# KGGR_D.net
KiCad netlist of a schematic drawn in EAGLE
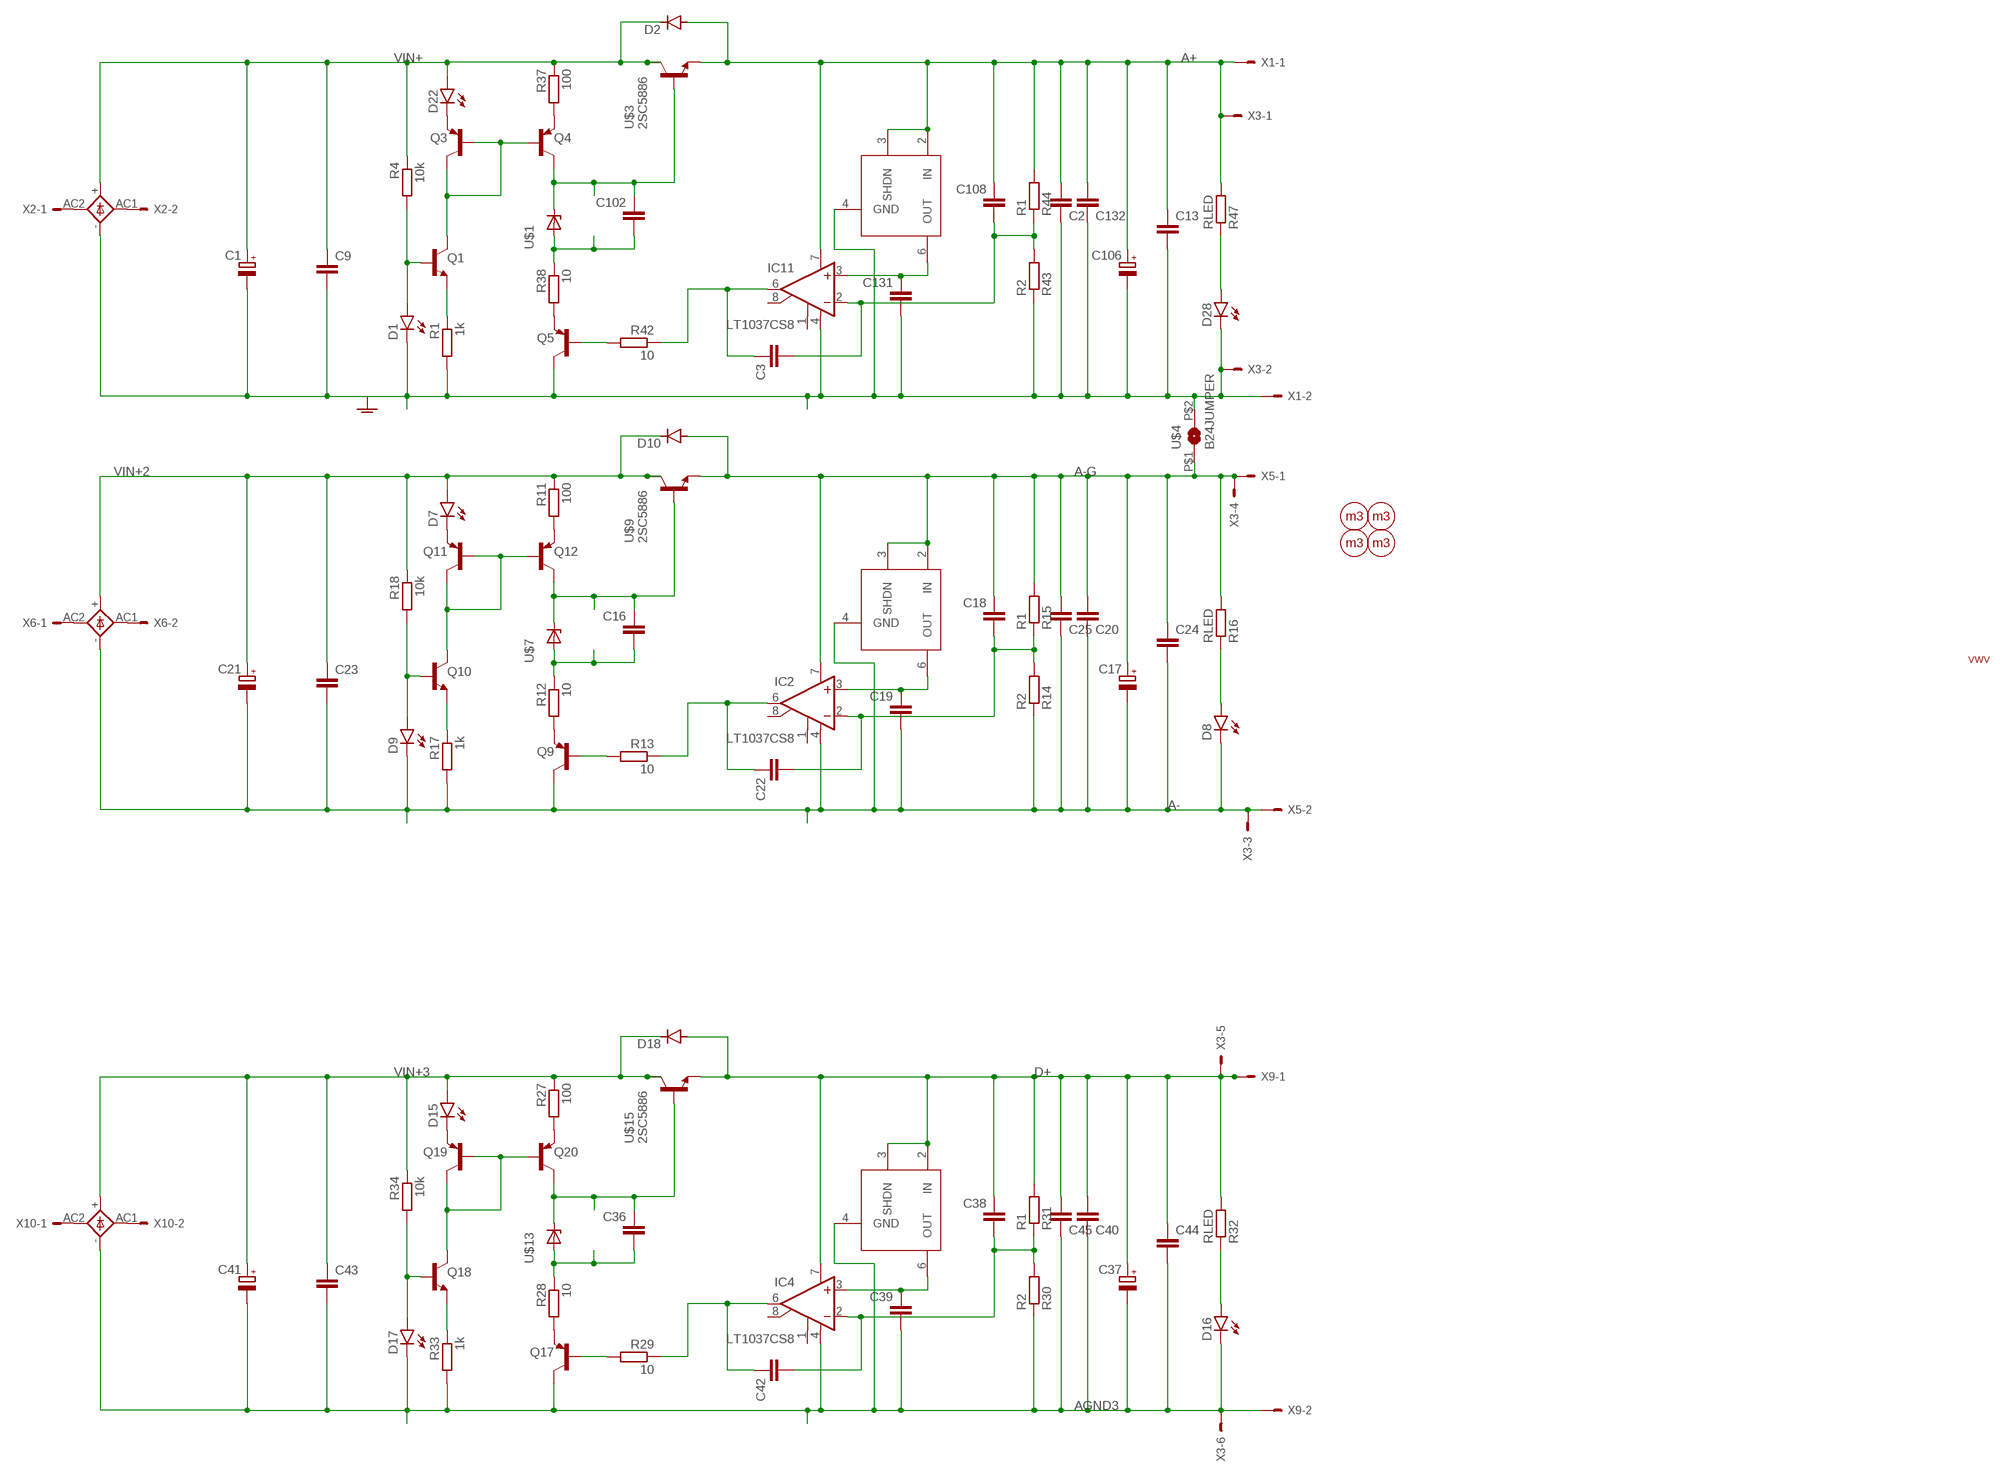
[diagram p0: schematic, sheet 1]

(export (version "E")
  (design (tool "Eeschema 10.0.6"))
  (components
    (comp (ref "B1")
      (value "GBU4")
      (footprint "eagle-import:GBU4S")
      (libsource (lib "eagle-import") (part "GBU4"))
    )
    (comp (ref "B3")
      (value "GBU4")
      (footprint "eagle-import:GBU4S")
      (libsource (lib "eagle-import") (part "GBU4"))
    )
    (comp (ref "B5")
      (value "GBU4")
      (footprint "eagle-import:GBU4S")
      (libsource (lib "eagle-import") (part "GBU4"))
    )
    (comp (ref "C1")
      (value "CPOL-EUE7.5-18")
      (footprint "eagle-import:E7,5-18")
      (libsource (lib "eagle-import") (part "CPOL-EUE7.5-18"))
    )
    (comp (ref "C2")
      (value "C-EUC0805")
      (footprint "eagle-import:C0805")
      (libsource (lib "eagle-import") (part "C-EUC0805"))
    )
    (comp (ref "C3")
      (value "C-EUC0805")
      (footprint "eagle-import:C0805")
      (libsource (lib "eagle-import") (part "C-EUC0805"))
    )
    (comp (ref "C9")
      (value "C-EU050-050X075")
      (footprint "eagle-import:C050-050X075")
      (libsource (lib "eagle-import") (part "C-EU050-050X075"))
    )
    (comp (ref "C13")
      (value "C-EU050-050X075")
      (footprint "eagle-import:C050-050X075")
      (libsource (lib "eagle-import") (part "C-EU050-050X075"))
    )
    (comp (ref "C16")
      (value "C-EUC0805")
      (footprint "eagle-import:C0805")
      (libsource (lib "eagle-import") (part "C-EUC0805"))
    )
    (comp (ref "C17")
      (value "CPOL-EUE5-10.5")
      (footprint "eagle-import:E5-10,5")
      (libsource (lib "eagle-import") (part "CPOL-EUE5-10.5"))
    )
    (comp (ref "C18")
      (value "C-EUC0805")
      (footprint "eagle-import:C0805")
      (libsource (lib "eagle-import") (part "C-EUC0805"))
    )
    (comp (ref "C19")
      (value "C-EUC1206")
      (footprint "eagle-import:C1206")
      (libsource (lib "eagle-import") (part "C-EUC1206"))
    )
    (comp (ref "C20")
      (value "C-EUC0805")
      (footprint "eagle-import:C0805")
      (libsource (lib "eagle-import") (part "C-EUC0805"))
    )
    (comp (ref "C21")
      (value "CPOL-EUE7.5-18")
      (footprint "eagle-import:E7,5-18")
      (libsource (lib "eagle-import") (part "CPOL-EUE7.5-18"))
    )
    (comp (ref "C22")
      (value "C-EUC0805")
      (footprint "eagle-import:C0805")
      (libsource (lib "eagle-import") (part "C-EUC0805"))
    )
    (comp (ref "C23")
      (value "C-EU050-050X075")
      (footprint "eagle-import:C050-050X075")
      (libsource (lib "eagle-import") (part "C-EU050-050X075"))
    )
    (comp (ref "C24")
      (value "C-EU050-050X075")
      (footprint "eagle-import:C050-050X075")
      (libsource (lib "eagle-import") (part "C-EU050-050X075"))
    )
    (comp (ref "C25")
      (value "C-EUC0805")
      (footprint "eagle-import:C0805")
      (libsource (lib "eagle-import") (part "C-EUC0805"))
    )
    (comp (ref "C36")
      (value "C-EUC0805")
      (footprint "eagle-import:C0805")
      (libsource (lib "eagle-import") (part "C-EUC0805"))
    )
    (comp (ref "C37")
      (value "CPOL-EUE5-10.5")
      (footprint "eagle-import:E5-10,5")
      (libsource (lib "eagle-import") (part "CPOL-EUE5-10.5"))
    )
    (comp (ref "C38")
      (value "C-EUC0805")
      (footprint "eagle-import:C0805")
      (libsource (lib "eagle-import") (part "C-EUC0805"))
    )
    (comp (ref "C39")
      (value "C-EUC1206")
      (footprint "eagle-import:C1206")
      (libsource (lib "eagle-import") (part "C-EUC1206"))
    )
    (comp (ref "C40")
      (value "C-EUC0805")
      (footprint "eagle-import:C0805")
      (libsource (lib "eagle-import") (part "C-EUC0805"))
    )
    (comp (ref "C41")
      (value "CPOL-EUE7.5-18")
      (footprint "eagle-import:E7,5-18")
      (libsource (lib "eagle-import") (part "CPOL-EUE7.5-18"))
    )
    (comp (ref "C42")
      (value "C-EUC0805")
      (footprint "eagle-import:C0805")
      (libsource (lib "eagle-import") (part "C-EUC0805"))
    )
    (comp (ref "C43")
      (value "C-EU050-050X075")
      (footprint "eagle-import:C050-050X075")
      (libsource (lib "eagle-import") (part "C-EU050-050X075"))
    )
    (comp (ref "C44")
      (value "C-EU050-050X075")
      (footprint "eagle-import:C050-050X075")
      (libsource (lib "eagle-import") (part "C-EU050-050X075"))
    )
    (comp (ref "C45")
      (value "C-EUC0805")
      (footprint "eagle-import:C0805")
      (libsource (lib "eagle-import") (part "C-EUC0805"))
    )
    (comp (ref "C102")
      (value "C-EUC0805")
      (footprint "eagle-import:C0805")
      (libsource (lib "eagle-import") (part "C-EUC0805"))
    )
    (comp (ref "C106")
      (value "CPOL-EUE5-10.5")
      (footprint "eagle-import:E5-10,5")
      (libsource (lib "eagle-import") (part "CPOL-EUE5-10.5"))
    )
    (comp (ref "C108")
      (value "C-EUC0805")
      (footprint "eagle-import:C0805")
      (libsource (lib "eagle-import") (part "C-EUC0805"))
    )
    (comp (ref "C131")
      (value "C-EUC1206")
      (footprint "eagle-import:C1206")
      (libsource (lib "eagle-import") (part "C-EUC1206"))
    )
    (comp (ref "C132")
      (value "C-EUC0805")
      (footprint "eagle-import:C0805")
      (libsource (lib "eagle-import") (part "C-EUC0805"))
    )
    (comp (ref "D1")
      (value "LEDVWV1206")
      (footprint "eagle-import:LED_SML1206")
      (libsource (lib "eagle-import") (part "LEDVWV1206"))
    )
    (comp (ref "D2")
      (value "DIODE-DO214AC")
      (footprint "eagle-import:DO214AC")
      (libsource (lib "eagle-import") (part "DIODE-DO214AC"))
    )
    (comp (ref "D7")
      (value "LEDVWV1206")
      (footprint "eagle-import:LED_SML1206")
      (libsource (lib "eagle-import") (part "LEDVWV1206"))
    )
    (comp (ref "D8")
      (value "LEDVWV1206")
      (footprint "eagle-import:LED_SML1206")
      (libsource (lib "eagle-import") (part "LEDVWV1206"))
    )
    (comp (ref "D9")
      (value "LEDVWV1206")
      (footprint "eagle-import:LED_SML1206")
      (libsource (lib "eagle-import") (part "LEDVWV1206"))
    )
    (comp (ref "D10")
      (value "DIODE-DO214AC")
      (footprint "eagle-import:DO214AC")
      (libsource (lib "eagle-import") (part "DIODE-DO214AC"))
    )
    (comp (ref "D15")
      (value "LEDVWV1206")
      (footprint "eagle-import:LED_SML1206")
      (libsource (lib "eagle-import") (part "LEDVWV1206"))
    )
    (comp (ref "D16")
      (value "LEDVWV1206")
      (footprint "eagle-import:LED_SML1206")
      (libsource (lib "eagle-import") (part "LEDVWV1206"))
    )
    (comp (ref "D17")
      (value "LEDVWV1206")
      (footprint "eagle-import:LED_SML1206")
      (libsource (lib "eagle-import") (part "LEDVWV1206"))
    )
    (comp (ref "D18")
      (value "DIODE-DO214AC")
      (footprint "eagle-import:DO214AC")
      (libsource (lib "eagle-import") (part "DIODE-DO214AC"))
    )
    (comp (ref "D22")
      (value "LEDVWV1206")
      (footprint "eagle-import:LED_SML1206")
      (libsource (lib "eagle-import") (part "LEDVWV1206"))
    )
    (comp (ref "D28")
      (value "LEDVWV1206")
      (footprint "eagle-import:LED_SML1206")
      (libsource (lib "eagle-import") (part "LEDVWV1206"))
    )
    (comp (ref "H1")
      (value "HOLE")
      (footprint "eagle-import:M3_HOLE")
      (libsource (lib "eagle-import") (part "HOLE"))
    )
    (comp (ref "H2")
      (value "HOLE")
      (footprint "eagle-import:M3_HOLE")
      (libsource (lib "eagle-import") (part "HOLE"))
    )
    (comp (ref "H3")
      (value "HOLE")
      (footprint "eagle-import:M3_HOLE")
      (libsource (lib "eagle-import") (part "HOLE"))
    )
    (comp (ref "H4")
      (value "HOLE")
      (footprint "eagle-import:M3_HOLE")
      (libsource (lib "eagle-import") (part "HOLE"))
    )
    (comp (ref "IC2")
      (value "LT1037CS8")
      (footprint "eagle-import:SOIC8")
      (libsource (lib "eagle-import") (part "LT10S837C"))
    )
    (comp (ref "IC4")
      (value "LT1037CS8")
      (footprint "eagle-import:SOIC8")
      (libsource (lib "eagle-import") (part "LT10S837C"))
    )
    (comp (ref "IC11")
      (value "LT1037CS8")
      (footprint "eagle-import:SOIC8")
      (libsource (lib "eagle-import") (part "LT10S837C"))
    )
    (comp (ref "Q1")
      (value "TRANSISTOR_BC847CLT1-NPN-SOT23-BEC")
      (footprint "eagle-import:TRANSISTOR_SOT23-BEC")
      (libsource (lib "eagle-import") (part "TRANSISTOR_-NPN-SOT23-BECBC847CLT1"))
    )
    (comp (ref "Q3")
      (value "TRANSISTOR_BC857C-PNP-SOT23-BEC")
      (footprint "eagle-import:TRANSISTOR_SOT23-BEC")
      (libsource (lib "eagle-import") (part "TRANSISTOR_-PNP-SOT23-BECBC857C"))
    )
    (comp (ref "Q4")
      (value "TRANSISTOR_BC857C-PNP-SOT23-BEC")
      (footprint "eagle-import:TRANSISTOR_SOT23-BEC")
      (libsource (lib "eagle-import") (part "TRANSISTOR_-PNP-SOT23-BECBC857C"))
    )
    (comp (ref "Q5")
      (value "TRANSISTOR_BC857C-PNP-SOT23-BEC")
      (footprint "eagle-import:TRANSISTOR_SOT23-BEC")
      (libsource (lib "eagle-import") (part "TRANSISTOR_-PNP-SOT23-BECBC857C"))
    )
    (comp (ref "Q9")
      (value "TRANSISTOR_BC857C-PNP-SOT23-BEC")
      (footprint "eagle-import:TRANSISTOR_SOT23-BEC")
      (libsource (lib "eagle-import") (part "TRANSISTOR_-PNP-SOT23-BECBC857C"))
    )
    (comp (ref "Q10")
      (value "TRANSISTOR_BC847CLT1-NPN-SOT23-BEC")
      (footprint "eagle-import:TRANSISTOR_SOT23-BEC")
      (libsource (lib "eagle-import") (part "TRANSISTOR_-NPN-SOT23-BECBC847CLT1"))
    )
    (comp (ref "Q11")
      (value "TRANSISTOR_BC857C-PNP-SOT23-BEC")
      (footprint "eagle-import:TRANSISTOR_SOT23-BEC")
      (libsource (lib "eagle-import") (part "TRANSISTOR_-PNP-SOT23-BECBC857C"))
    )
    (comp (ref "Q12")
      (value "TRANSISTOR_BC857C-PNP-SOT23-BEC")
      (footprint "eagle-import:TRANSISTOR_SOT23-BEC")
      (libsource (lib "eagle-import") (part "TRANSISTOR_-PNP-SOT23-BECBC857C"))
    )
    (comp (ref "Q17")
      (value "TRANSISTOR_BC857C-PNP-SOT23-BEC")
      (footprint "eagle-import:TRANSISTOR_SOT23-BEC")
      (libsource (lib "eagle-import") (part "TRANSISTOR_-PNP-SOT23-BECBC857C"))
    )
    (comp (ref "Q18")
      (value "TRANSISTOR_BC847CLT1-NPN-SOT23-BEC")
      (footprint "eagle-import:TRANSISTOR_SOT23-BEC")
      (libsource (lib "eagle-import") (part "TRANSISTOR_-NPN-SOT23-BECBC847CLT1"))
    )
    (comp (ref "Q19")
      (value "TRANSISTOR_BC857C-PNP-SOT23-BEC")
      (footprint "eagle-import:TRANSISTOR_SOT23-BEC")
      (libsource (lib "eagle-import") (part "TRANSISTOR_-PNP-SOT23-BECBC857C"))
    )
    (comp (ref "Q20")
      (value "TRANSISTOR_BC857C-PNP-SOT23-BEC")
      (footprint "eagle-import:TRANSISTOR_SOT23-BEC")
      (libsource (lib "eagle-import") (part "TRANSISTOR_-PNP-SOT23-BECBC857C"))
    )
    (comp (ref "R1")
      (value "1k")
      (footprint "eagle-import:MINI_MELF-0204W")
      (libsource (lib "eagle-import") (part "R-EU_MELF0204W"))
    )
    (comp (ref "R4")
      (value "10k")
      (footprint "eagle-import:MINI_MELF-0204W")
      (libsource (lib "eagle-import") (part "R-EU_MELF0204W"))
    )
    (comp (ref "R11")
      (value "100")
      (footprint "eagle-import:MINI_MELF-0204W")
      (libsource (lib "eagle-import") (part "R-EU_MELF0204W"))
    )
    (comp (ref "R12")
      (value "10")
      (footprint "eagle-import:MINI_MELF-0204W")
      (libsource (lib "eagle-import") (part "R-EU_MELF0204W"))
    )
    (comp (ref "R13")
      (value "10")
      (footprint "eagle-import:MINI_MELF-0204W")
      (libsource (lib "eagle-import") (part "R-EU_MELF0204W"))
    )
    (comp (ref "R14")
      (value "R2")
      (footprint "eagle-import:MINI_MELF-0204W")
      (libsource (lib "eagle-import") (part "R-EU_MELF0204W"))
    )
    (comp (ref "R15")
      (value "R1")
      (footprint "eagle-import:MINI_MELF-0204W")
      (libsource (lib "eagle-import") (part "R-EU_MELF0204W"))
    )
    (comp (ref "R16")
      (value "RLED")
      (footprint "eagle-import:MINI_MELF-0204W")
      (libsource (lib "eagle-import") (part "R-EU_MELF0204W"))
    )
    (comp (ref "R17")
      (value "1k")
      (footprint "eagle-import:MINI_MELF-0204W")
      (libsource (lib "eagle-import") (part "R-EU_MELF0204W"))
    )
    (comp (ref "R18")
      (value "10k")
      (footprint "eagle-import:MINI_MELF-0204W")
      (libsource (lib "eagle-import") (part "R-EU_MELF0204W"))
    )
    (comp (ref "R27")
      (value "100")
      (footprint "eagle-import:MINI_MELF-0204W")
      (libsource (lib "eagle-import") (part "R-EU_MELF0204W"))
    )
    (comp (ref "R28")
      (value "10")
      (footprint "eagle-import:MINI_MELF-0204W")
      (libsource (lib "eagle-import") (part "R-EU_MELF0204W"))
    )
    (comp (ref "R29")
      (value "10")
      (footprint "eagle-import:MINI_MELF-0204W")
      (libsource (lib "eagle-import") (part "R-EU_MELF0204W"))
    )
    (comp (ref "R30")
      (value "R2")
      (footprint "eagle-import:MINI_MELF-0204W")
      (libsource (lib "eagle-import") (part "R-EU_MELF0204W"))
    )
    (comp (ref "R31")
      (value "R1")
      (footprint "eagle-import:MINI_MELF-0204W")
      (libsource (lib "eagle-import") (part "R-EU_MELF0204W"))
    )
    (comp (ref "R32")
      (value "RLED")
      (footprint "eagle-import:MINI_MELF-0204W")
      (libsource (lib "eagle-import") (part "R-EU_MELF0204W"))
    )
    (comp (ref "R33")
      (value "1k")
      (footprint "eagle-import:MINI_MELF-0204W")
      (libsource (lib "eagle-import") (part "R-EU_MELF0204W"))
    )
    (comp (ref "R34")
      (value "10k")
      (footprint "eagle-import:MINI_MELF-0204W")
      (libsource (lib "eagle-import") (part "R-EU_MELF0204W"))
    )
    (comp (ref "R37")
      (value "100")
      (footprint "eagle-import:MINI_MELF-0204W")
      (libsource (lib "eagle-import") (part "R-EU_MELF0204W"))
    )
    (comp (ref "R38")
      (value "10")
      (footprint "eagle-import:MINI_MELF-0204W")
      (libsource (lib "eagle-import") (part "R-EU_MELF0204W"))
    )
    (comp (ref "R42")
      (value "10")
      (footprint "eagle-import:MINI_MELF-0204W")
      (libsource (lib "eagle-import") (part "R-EU_MELF0204W"))
    )
    (comp (ref "R43")
      (value "R2")
      (footprint "eagle-import:MINI_MELF-0204W")
      (libsource (lib "eagle-import") (part "R-EU_MELF0204W"))
    )
    (comp (ref "R44")
      (value "R1")
      (footprint "eagle-import:MINI_MELF-0204W")
      (libsource (lib "eagle-import") (part "R-EU_MELF0204W"))
    )
    (comp (ref "R47")
      (value "RLED")
      (footprint "eagle-import:MINI_MELF-0204W")
      (libsource (lib "eagle-import") (part "R-EU_MELF0204W"))
    )
    (comp (ref "S1")
      (value "VWV")
      (footprint "eagle-import:VWV")
      (libsource (lib "eagle-import") (part "VWV"))
    )
    (comp (ref "U$1")
      (value "ADR504X")
      (footprint "eagle-import:SOT-23")
      (libsource (lib "eagle-import") (part "ADR504X"))
    )
    (comp (ref "U$2")
      (value "LT6657")
      (footprint "eagle-import:MSOP8")
      (libsource (lib "eagle-import") (part "LT6657"))
    )
    (comp (ref "U$3")
      (value "2SC5886")
      (footprint "eagle-import:NEW-PWMOLD")
      (libsource (lib "eagle-import") (part "2SC5886"))
    )
    (comp (ref "U$4")
      (value "B24JUMPER")
      (footprint "eagle-import:B24J")
      (libsource (lib "eagle-import") (part "B24JUMPER"))
    )
    (comp (ref "U$7")
      (value "ADR504X")
      (footprint "eagle-import:SOT-23")
      (libsource (lib "eagle-import") (part "ADR504X"))
    )
    (comp (ref "U$8")
      (value "LT6657")
      (footprint "eagle-import:MSOP8")
      (libsource (lib "eagle-import") (part "LT6657"))
    )
    (comp (ref "U$9")
      (value "2SC5886")
      (footprint "eagle-import:NEW-PWMOLD")
      (libsource (lib "eagle-import") (part "2SC5886"))
    )
    (comp (ref "U$13")
      (value "ADR504X")
      (footprint "eagle-import:SOT-23")
      (libsource (lib "eagle-import") (part "ADR504X"))
    )
    (comp (ref "U$14")
      (value "LT6657")
      (footprint "eagle-import:MSOP8")
      (libsource (lib "eagle-import") (part "LT6657"))
    )
    (comp (ref "U$15")
      (value "2SC5886")
      (footprint "eagle-import:NEW-PWMOLD")
      (libsource (lib "eagle-import") (part "2SC5886"))
    )
    (comp (ref "X1")
      (value "KK-156-2")
      (footprint "eagle-import:KK-156-2")
      (fields (field (name "MF") "MOLEX"))
      (libsource (lib "eagle-import") (part "KK-156-2"))
    )
    (comp (ref "X2")
      (value "KK-156-2")
      (footprint "eagle-import:KK-156-2")
      (fields (field (name "MF") "MOLEX"))
      (libsource (lib "eagle-import") (part "KK-156-2"))
    )
    (comp (ref "X3")
      (value "KK-156-6")
      (footprint "eagle-import:KK-156-6")
      (fields (field (name "MF") "MOLEX"))
      (libsource (lib "eagle-import") (part "KK-156-6"))
    )
    (comp (ref "X5")
      (value "KK-156-2")
      (footprint "eagle-import:KK-156-2")
      (fields (field (name "MF") "MOLEX"))
      (libsource (lib "eagle-import") (part "KK-156-2"))
    )
    (comp (ref "X6")
      (value "KK-156-2")
      (footprint "eagle-import:KK-156-2")
      (fields (field (name "MF") "MOLEX"))
      (libsource (lib "eagle-import") (part "KK-156-2"))
    )
    (comp (ref "X9")
      (value "KK-156-2")
      (footprint "eagle-import:KK-156-2")
      (fields (field (name "MF") "MOLEX"))
      (libsource (lib "eagle-import") (part "KK-156-2"))
    )
    (comp (ref "X10")
      (value "KK-156-2")
      (footprint "eagle-import:KK-156-2")
      (fields (field (name "MF") "MOLEX"))
      (libsource (lib "eagle-import") (part "KK-156-2"))
    )
  )
  (nets
    (net (code "1") (name "/A+") (class "Default")
      (node (ref "C106") (pin "+") (pinfunction "+_+") (pintype "passive"))
      (node (ref "C108") (pin "1") (pinfunction "1_1") (pintype "passive"))
      (node (ref "C13") (pin "1") (pinfunction "1_1") (pintype "passive"))
      (node (ref "C132") (pin "2") (pinfunction "2_2") (pintype "passive"))
      (node (ref "C2") (pin "2") (pinfunction "2_2") (pintype "passive"))
      (node (ref "D2") (pin "A") (pinfunction "A_A") (pintype "passive"))
      (node (ref "IC11") (pin "7") (pinfunction "V+_7") (pintype "power_in"))
      (node (ref "R44") (pin "2") (pinfunction "2_2") (pintype "passive"))
      (node (ref "R47") (pin "2") (pinfunction "2_2") (pintype "passive"))
      (node (ref "U$2") (pin "2") (pinfunction "IN_2") (pintype "bidirectional"))
      (node (ref "U$2") (pin "3") (pinfunction "SHDN_3") (pintype "bidirectional"))
      (node (ref "U$3") (pin "3") (pinfunction "E_3") (pintype "passive"))
      (node (ref "X1") (pin "1") (pinfunction "S_1") (pintype "passive"))
      (node (ref "X3") (pin "1") (pinfunction "S_1") (pintype "passive"))
    )
    (net (code "2") (name "/A-") (class "Default")
      (node (ref "B3") (pin "-") (pinfunction "-_-") (pintype "passive"))
      (node (ref "C17") (pin "-") (pinfunction "-_-") (pintype "passive"))
      (node (ref "C19") (pin "2") (pinfunction "2_2") (pintype "passive"))
      (node (ref "C20") (pin "1") (pinfunction "1_1") (pintype "passive"))
      (node (ref "C21") (pin "-") (pinfunction "-_-") (pintype "passive"))
      (node (ref "C23") (pin "2") (pinfunction "2_2") (pintype "passive"))
      (node (ref "C24") (pin "2") (pinfunction "2_2") (pintype "passive"))
      (node (ref "C25") (pin "1") (pinfunction "1_1") (pintype "passive"))
      (node (ref "D8") (pin "C") (pinfunction "C_C") (pintype "passive"))
      (node (ref "D9") (pin "C") (pinfunction "C_C") (pintype "passive"))
      (node (ref "IC2") (pin "4") (pinfunction "V-_4") (pintype "power_in"))
      (node (ref "Q9") (pin "C") (pinfunction "C_C") (pintype "passive"))
      (node (ref "R14") (pin "1") (pinfunction "1_1") (pintype "passive"))
      (node (ref "R17") (pin "2") (pinfunction "2_2") (pintype "passive"))
      (node (ref "U$8") (pin "4") (pinfunction "GND_4") (pintype "bidirectional"))
      (node (ref "X3") (pin "3") (pinfunction "S_3") (pintype "passive"))
      (node (ref "X5") (pin "2") (pinfunction "S_2") (pintype "passive"))
    )
    (net (code "3") (name "/A-G") (class "Default")
      (node (ref "C17") (pin "+") (pinfunction "+_+") (pintype "passive"))
      (node (ref "C18") (pin "1") (pinfunction "1_1") (pintype "passive"))
      (node (ref "C20") (pin "2") (pinfunction "2_2") (pintype "passive"))
      (node (ref "C24") (pin "1") (pinfunction "1_1") (pintype "passive"))
      (node (ref "C25") (pin "2") (pinfunction "2_2") (pintype "passive"))
      (node (ref "D10") (pin "A") (pinfunction "A_A") (pintype "passive"))
      (node (ref "IC2") (pin "7") (pinfunction "V+_7") (pintype "power_in"))
      (node (ref "R15") (pin "2") (pinfunction "2_2") (pintype "passive"))
      (node (ref "R16") (pin "2") (pinfunction "2_2") (pintype "passive"))
      (node (ref "U$4") (pin "P$1") (pinfunction "1_P$1") (pintype "passive"))
      (node (ref "U$8") (pin "2") (pinfunction "IN_2") (pintype "bidirectional"))
      (node (ref "U$8") (pin "3") (pinfunction "SHDN_3") (pintype "bidirectional"))
      (node (ref "U$9") (pin "3") (pinfunction "E_3") (pintype "passive"))
      (node (ref "X3") (pin "4") (pinfunction "S_4") (pintype "passive"))
      (node (ref "X5") (pin "1") (pinfunction "S_1") (pintype "passive"))
    )
    (net (code "4") (name "/AGND3") (class "Default")
      (node (ref "B5") (pin "-") (pinfunction "-_-") (pintype "passive"))
      (node (ref "C37") (pin "-") (pinfunction "-_-") (pintype "passive"))
      (node (ref "C39") (pin "2") (pinfunction "2_2") (pintype "passive"))
      (node (ref "C40") (pin "1") (pinfunction "1_1") (pintype "passive"))
      (node (ref "C41") (pin "-") (pinfunction "-_-") (pintype "passive"))
      (node (ref "C43") (pin "2") (pinfunction "2_2") (pintype "passive"))
      (node (ref "C44") (pin "2") (pinfunction "2_2") (pintype "passive"))
      (node (ref "C45") (pin "1") (pinfunction "1_1") (pintype "passive"))
      (node (ref "D16") (pin "C") (pinfunction "C_C") (pintype "passive"))
      (node (ref "D17") (pin "C") (pinfunction "C_C") (pintype "passive"))
      (node (ref "IC4") (pin "4") (pinfunction "V-_4") (pintype "power_in"))
      (node (ref "Q17") (pin "C") (pinfunction "C_C") (pintype "passive"))
      (node (ref "R30") (pin "1") (pinfunction "1_1") (pintype "passive"))
      (node (ref "R33") (pin "2") (pinfunction "2_2") (pintype "passive"))
      (node (ref "U$14") (pin "4") (pinfunction "GND_4") (pintype "bidirectional"))
      (node (ref "X3") (pin "6") (pinfunction "S_6") (pintype "passive"))
      (node (ref "X9") (pin "2") (pinfunction "S_2") (pintype "passive"))
    )
    (net (code "5") (name "/D+") (class "Default")
      (node (ref "C37") (pin "+") (pinfunction "+_+") (pintype "passive"))
      (node (ref "C38") (pin "1") (pinfunction "1_1") (pintype "passive"))
      (node (ref "C40") (pin "2") (pinfunction "2_2") (pintype "passive"))
      (node (ref "C44") (pin "1") (pinfunction "1_1") (pintype "passive"))
      (node (ref "C45") (pin "2") (pinfunction "2_2") (pintype "passive"))
      (node (ref "D18") (pin "A") (pinfunction "A_A") (pintype "passive"))
      (node (ref "IC4") (pin "7") (pinfunction "V+_7") (pintype "power_in"))
      (node (ref "R31") (pin "2") (pinfunction "2_2") (pintype "passive"))
      (node (ref "R32") (pin "2") (pinfunction "2_2") (pintype "passive"))
      (node (ref "U$14") (pin "2") (pinfunction "IN_2") (pintype "bidirectional"))
      (node (ref "U$14") (pin "3") (pinfunction "SHDN_3") (pintype "bidirectional"))
      (node (ref "U$15") (pin "3") (pinfunction "E_3") (pintype "passive"))
      (node (ref "X3") (pin "5") (pinfunction "S_5") (pintype "passive"))
      (node (ref "X9") (pin "1") (pinfunction "S_1") (pintype "passive"))
    )
    (net (code "6") (name "/VIN+") (class "Default")
      (node (ref "B1") (pin "+") (pinfunction "+_+") (pintype "passive"))
      (node (ref "C1") (pin "+") (pinfunction "+_+") (pintype "passive"))
      (node (ref "C9") (pin "1") (pinfunction "1_1") (pintype "passive"))
      (node (ref "D2") (pin "C") (pinfunction "C_C") (pintype "passive"))
      (node (ref "D22") (pin "A") (pinfunction "A_A") (pintype "passive"))
      (node (ref "R37") (pin "1") (pinfunction "1_1") (pintype "passive"))
      (node (ref "R4") (pin "1") (pinfunction "1_1") (pintype "passive"))
      (node (ref "U$3") (pin "2") (pinfunction "C_2") (pintype "passive"))
      (node (ref "U$3") (pin "4") (pinfunction "C_4") (pintype "passive"))
      (node (ref "U$3") (pin "P$1") (pinfunction "C_P$1") (pintype "passive"))
      (node (ref "U$3") (pin "P$10") (pinfunction "C_P$10") (pintype "passive"))
      (node (ref "U$3") (pin "P$11") (pinfunction "C_P$11") (pintype "passive"))
      (node (ref "U$3") (pin "P$12") (pinfunction "C_P$12") (pintype "passive"))
      (node (ref "U$3") (pin "P$13") (pinfunction "C_P$13") (pintype "passive"))
      (node (ref "U$3") (pin "P$14") (pinfunction "C_P$14") (pintype "passive"))
      (node (ref "U$3") (pin "P$15") (pinfunction "C_P$15") (pintype "passive"))
      (node (ref "U$3") (pin "P$16") (pinfunction "C_P$16") (pintype "passive"))
      (node (ref "U$3") (pin "P$17") (pinfunction "C_P$17") (pintype "passive"))
      (node (ref "U$3") (pin "P$18") (pinfunction "C_P$18") (pintype "passive"))
      (node (ref "U$3") (pin "P$19") (pinfunction "C_P$19") (pintype "passive"))
      (node (ref "U$3") (pin "P$2") (pinfunction "C_P$2") (pintype "passive"))
      (node (ref "U$3") (pin "P$20") (pinfunction "C_P$20") (pintype "passive"))
      (node (ref "U$3") (pin "P$21") (pinfunction "C_P$21") (pintype "passive"))
      (node (ref "U$3") (pin "P$22") (pinfunction "C_P$22") (pintype "passive"))
      (node (ref "U$3") (pin "P$23") (pinfunction "C_P$23") (pintype "passive"))
      (node (ref "U$3") (pin "P$24") (pinfunction "C_P$24") (pintype "passive"))
      (node (ref "U$3") (pin "P$25") (pinfunction "C_P$25") (pintype "passive"))
      (node (ref "U$3") (pin "P$26") (pinfunction "C_P$26") (pintype "passive"))
      (node (ref "U$3") (pin "P$27") (pinfunction "C_P$27") (pintype "passive"))
      (node (ref "U$3") (pin "P$28") (pinfunction "C_P$28") (pintype "passive"))
      (node (ref "U$3") (pin "P$29") (pinfunction "C_P$29") (pintype "passive"))
      (node (ref "U$3") (pin "P$3") (pinfunction "C_P$3") (pintype "passive"))
      (node (ref "U$3") (pin "P$30") (pinfunction "C_P$30") (pintype "passive"))
      (node (ref "U$3") (pin "P$31") (pinfunction "C_P$31") (pintype "passive"))
      (node (ref "U$3") (pin "P$32") (pinfunction "C_P$32") (pintype "passive"))
      (node (ref "U$3") (pin "P$33") (pinfunction "C_P$33") (pintype "passive"))
      (node (ref "U$3") (pin "P$34") (pinfunction "C_P$34") (pintype "passive"))
      (node (ref "U$3") (pin "P$35") (pinfunction "C_P$35") (pintype "passive"))
      (node (ref "U$3") (pin "P$36") (pinfunction "C_P$36") (pintype "passive"))
      (node (ref "U$3") (pin "P$37") (pinfunction "C_P$37") (pintype "passive"))
      (node (ref "U$3") (pin "P$38") (pinfunction "C_P$38") (pintype "passive"))
      (node (ref "U$3") (pin "P$39") (pinfunction "C_P$39") (pintype "passive"))
      (node (ref "U$3") (pin "P$4") (pinfunction "C_P$4") (pintype "passive"))
      (node (ref "U$3") (pin "P$40") (pinfunction "C_P$40") (pintype "passive"))
      (node (ref "U$3") (pin "P$41") (pinfunction "C_P$41") (pintype "passive"))
      (node (ref "U$3") (pin "P$42") (pinfunction "C_P$42") (pintype "passive"))
      (node (ref "U$3") (pin "P$43") (pinfunction "C_P$43") (pintype "passive"))
      (node (ref "U$3") (pin "P$44") (pinfunction "C_P$44") (pintype "passive"))
      (node (ref "U$3") (pin "P$45") (pinfunction "C_P$45") (pintype "passive"))
      (node (ref "U$3") (pin "P$46") (pinfunction "C_P$46") (pintype "passive"))
      (node (ref "U$3") (pin "P$47") (pinfunction "C_P$47") (pintype "passive"))
      (node (ref "U$3") (pin "P$48") (pinfunction "C_P$48") (pintype "passive"))
      (node (ref "U$3") (pin "P$49") (pinfunction "C_P$49") (pintype "passive"))
      (node (ref "U$3") (pin "P$5") (pinfunction "C_P$5") (pintype "passive"))
      (node (ref "U$3") (pin "P$50") (pinfunction "C_P$50") (pintype "passive"))
      (node (ref "U$3") (pin "P$51") (pinfunction "C_P$51") (pintype "passive"))
      (node (ref "U$3") (pin "P$52") (pinfunction "C_P$52") (pintype "passive"))
      (node (ref "U$3") (pin "P$53") (pinfunction "C_P$53") (pintype "passive"))
      (node (ref "U$3") (pin "P$54") (pinfunction "C_P$54") (pintype "passive"))
      (node (ref "U$3") (pin "P$55") (pinfunction "C_P$55") (pintype "passive"))
      (node (ref "U$3") (pin "P$56") (pinfunction "C_P$56") (pintype "passive"))
      (node (ref "U$3") (pin "P$57") (pinfunction "C_P$57") (pintype "passive"))
      (node (ref "U$3") (pin "P$58") (pinfunction "C_P$58") (pintype "passive"))
      (node (ref "U$3") (pin "P$59") (pinfunction "C_P$59") (pintype "passive"))
      (node (ref "U$3") (pin "P$6") (pinfunction "C_P$6") (pintype "passive"))
      (node (ref "U$3") (pin "P$60") (pinfunction "C_P$60") (pintype "passive"))
      (node (ref "U$3") (pin "P$61") (pinfunction "C_P$61") (pintype "passive"))
      (node (ref "U$3") (pin "P$62") (pinfunction "C_P$62") (pintype "passive"))
      (node (ref "U$3") (pin "P$63") (pinfunction "C_P$63") (pintype "passive"))
      (node (ref "U$3") (pin "P$7") (pinfunction "C_P$7") (pintype "passive"))
      (node (ref "U$3") (pin "P$8") (pinfunction "C_P$8") (pintype "passive"))
      (node (ref "U$3") (pin "P$9") (pinfunction "C_P$9") (pintype "passive"))
    )
    (net (code "7") (name "/VIN+2") (class "Default")
      (node (ref "B3") (pin "+") (pinfunction "+_+") (pintype "passive"))
      (node (ref "C21") (pin "+") (pinfunction "+_+") (pintype "passive"))
      (node (ref "C23") (pin "1") (pinfunction "1_1") (pintype "passive"))
      (node (ref "D10") (pin "C") (pinfunction "C_C") (pintype "passive"))
      (node (ref "D7") (pin "A") (pinfunction "A_A") (pintype "passive"))
      (node (ref "R11") (pin "1") (pinfunction "1_1") (pintype "passive"))
      (node (ref "R18") (pin "1") (pinfunction "1_1") (pintype "passive"))
      (node (ref "U$9") (pin "2") (pinfunction "C_2") (pintype "passive"))
      (node (ref "U$9") (pin "4") (pinfunction "C_4") (pintype "passive"))
      (node (ref "U$9") (pin "P$1") (pinfunction "C_P$1") (pintype "passive"))
      (node (ref "U$9") (pin "P$10") (pinfunction "C_P$10") (pintype "passive"))
      (node (ref "U$9") (pin "P$11") (pinfunction "C_P$11") (pintype "passive"))
      (node (ref "U$9") (pin "P$12") (pinfunction "C_P$12") (pintype "passive"))
      (node (ref "U$9") (pin "P$13") (pinfunction "C_P$13") (pintype "passive"))
      (node (ref "U$9") (pin "P$14") (pinfunction "C_P$14") (pintype "passive"))
      (node (ref "U$9") (pin "P$15") (pinfunction "C_P$15") (pintype "passive"))
      (node (ref "U$9") (pin "P$16") (pinfunction "C_P$16") (pintype "passive"))
      (node (ref "U$9") (pin "P$17") (pinfunction "C_P$17") (pintype "passive"))
      (node (ref "U$9") (pin "P$18") (pinfunction "C_P$18") (pintype "passive"))
      (node (ref "U$9") (pin "P$19") (pinfunction "C_P$19") (pintype "passive"))
      (node (ref "U$9") (pin "P$2") (pinfunction "C_P$2") (pintype "passive"))
      (node (ref "U$9") (pin "P$20") (pinfunction "C_P$20") (pintype "passive"))
      (node (ref "U$9") (pin "P$21") (pinfunction "C_P$21") (pintype "passive"))
      (node (ref "U$9") (pin "P$22") (pinfunction "C_P$22") (pintype "passive"))
      (node (ref "U$9") (pin "P$23") (pinfunction "C_P$23") (pintype "passive"))
      (node (ref "U$9") (pin "P$24") (pinfunction "C_P$24") (pintype "passive"))
      (node (ref "U$9") (pin "P$25") (pinfunction "C_P$25") (pintype "passive"))
      (node (ref "U$9") (pin "P$26") (pinfunction "C_P$26") (pintype "passive"))
      (node (ref "U$9") (pin "P$27") (pinfunction "C_P$27") (pintype "passive"))
      (node (ref "U$9") (pin "P$28") (pinfunction "C_P$28") (pintype "passive"))
      (node (ref "U$9") (pin "P$29") (pinfunction "C_P$29") (pintype "passive"))
      (node (ref "U$9") (pin "P$3") (pinfunction "C_P$3") (pintype "passive"))
      (node (ref "U$9") (pin "P$30") (pinfunction "C_P$30") (pintype "passive"))
      (node (ref "U$9") (pin "P$31") (pinfunction "C_P$31") (pintype "passive"))
      (node (ref "U$9") (pin "P$32") (pinfunction "C_P$32") (pintype "passive"))
      (node (ref "U$9") (pin "P$33") (pinfunction "C_P$33") (pintype "passive"))
      (node (ref "U$9") (pin "P$34") (pinfunction "C_P$34") (pintype "passive"))
      (node (ref "U$9") (pin "P$35") (pinfunction "C_P$35") (pintype "passive"))
      (node (ref "U$9") (pin "P$36") (pinfunction "C_P$36") (pintype "passive"))
      (node (ref "U$9") (pin "P$37") (pinfunction "C_P$37") (pintype "passive"))
      (node (ref "U$9") (pin "P$38") (pinfunction "C_P$38") (pintype "passive"))
      (node (ref "U$9") (pin "P$39") (pinfunction "C_P$39") (pintype "passive"))
      (node (ref "U$9") (pin "P$4") (pinfunction "C_P$4") (pintype "passive"))
      (node (ref "U$9") (pin "P$40") (pinfunction "C_P$40") (pintype "passive"))
      (node (ref "U$9") (pin "P$41") (pinfunction "C_P$41") (pintype "passive"))
      (node (ref "U$9") (pin "P$42") (pinfunction "C_P$42") (pintype "passive"))
      (node (ref "U$9") (pin "P$43") (pinfunction "C_P$43") (pintype "passive"))
      (node (ref "U$9") (pin "P$44") (pinfunction "C_P$44") (pintype "passive"))
      (node (ref "U$9") (pin "P$45") (pinfunction "C_P$45") (pintype "passive"))
      (node (ref "U$9") (pin "P$46") (pinfunction "C_P$46") (pintype "passive"))
      (node (ref "U$9") (pin "P$47") (pinfunction "C_P$47") (pintype "passive"))
      (node (ref "U$9") (pin "P$48") (pinfunction "C_P$48") (pintype "passive"))
      (node (ref "U$9") (pin "P$49") (pinfunction "C_P$49") (pintype "passive"))
      (node (ref "U$9") (pin "P$5") (pinfunction "C_P$5") (pintype "passive"))
      (node (ref "U$9") (pin "P$50") (pinfunction "C_P$50") (pintype "passive"))
      (node (ref "U$9") (pin "P$51") (pinfunction "C_P$51") (pintype "passive"))
      (node (ref "U$9") (pin "P$52") (pinfunction "C_P$52") (pintype "passive"))
      (node (ref "U$9") (pin "P$53") (pinfunction "C_P$53") (pintype "passive"))
      (node (ref "U$9") (pin "P$54") (pinfunction "C_P$54") (pintype "passive"))
      (node (ref "U$9") (pin "P$55") (pinfunction "C_P$55") (pintype "passive"))
      (node (ref "U$9") (pin "P$56") (pinfunction "C_P$56") (pintype "passive"))
      (node (ref "U$9") (pin "P$57") (pinfunction "C_P$57") (pintype "passive"))
      (node (ref "U$9") (pin "P$58") (pinfunction "C_P$58") (pintype "passive"))
      (node (ref "U$9") (pin "P$59") (pinfunction "C_P$59") (pintype "passive"))
      (node (ref "U$9") (pin "P$6") (pinfunction "C_P$6") (pintype "passive"))
      (node (ref "U$9") (pin "P$60") (pinfunction "C_P$60") (pintype "passive"))
      (node (ref "U$9") (pin "P$61") (pinfunction "C_P$61") (pintype "passive"))
      (node (ref "U$9") (pin "P$62") (pinfunction "C_P$62") (pintype "passive"))
      (node (ref "U$9") (pin "P$63") (pinfunction "C_P$63") (pintype "passive"))
      (node (ref "U$9") (pin "P$7") (pinfunction "C_P$7") (pintype "passive"))
      (node (ref "U$9") (pin "P$8") (pinfunction "C_P$8") (pintype "passive"))
      (node (ref "U$9") (pin "P$9") (pinfunction "C_P$9") (pintype "passive"))
    )
    (net (code "8") (name "/VIN+3") (class "Default")
      (node (ref "B5") (pin "+") (pinfunction "+_+") (pintype "passive"))
      (node (ref "C41") (pin "+") (pinfunction "+_+") (pintype "passive"))
      (node (ref "C43") (pin "1") (pinfunction "1_1") (pintype "passive"))
      (node (ref "D15") (pin "A") (pinfunction "A_A") (pintype "passive"))
      (node (ref "D18") (pin "C") (pinfunction "C_C") (pintype "passive"))
      (node (ref "R27") (pin "1") (pinfunction "1_1") (pintype "passive"))
      (node (ref "R34") (pin "1") (pinfunction "1_1") (pintype "passive"))
      (node (ref "U$15") (pin "2") (pinfunction "C_2") (pintype "passive"))
      (node (ref "U$15") (pin "4") (pinfunction "C_4") (pintype "passive"))
      (node (ref "U$15") (pin "P$1") (pinfunction "C_P$1") (pintype "passive"))
      (node (ref "U$15") (pin "P$10") (pinfunction "C_P$10") (pintype "passive"))
      (node (ref "U$15") (pin "P$11") (pinfunction "C_P$11") (pintype "passive"))
      (node (ref "U$15") (pin "P$12") (pinfunction "C_P$12") (pintype "passive"))
      (node (ref "U$15") (pin "P$13") (pinfunction "C_P$13") (pintype "passive"))
      (node (ref "U$15") (pin "P$14") (pinfunction "C_P$14") (pintype "passive"))
      (node (ref "U$15") (pin "P$15") (pinfunction "C_P$15") (pintype "passive"))
      (node (ref "U$15") (pin "P$16") (pinfunction "C_P$16") (pintype "passive"))
      (node (ref "U$15") (pin "P$17") (pinfunction "C_P$17") (pintype "passive"))
      (node (ref "U$15") (pin "P$18") (pinfunction "C_P$18") (pintype "passive"))
      (node (ref "U$15") (pin "P$19") (pinfunction "C_P$19") (pintype "passive"))
      (node (ref "U$15") (pin "P$2") (pinfunction "C_P$2") (pintype "passive"))
      (node (ref "U$15") (pin "P$20") (pinfunction "C_P$20") (pintype "passive"))
      (node (ref "U$15") (pin "P$21") (pinfunction "C_P$21") (pintype "passive"))
      (node (ref "U$15") (pin "P$22") (pinfunction "C_P$22") (pintype "passive"))
      (node (ref "U$15") (pin "P$23") (pinfunction "C_P$23") (pintype "passive"))
      (node (ref "U$15") (pin "P$24") (pinfunction "C_P$24") (pintype "passive"))
      (node (ref "U$15") (pin "P$25") (pinfunction "C_P$25") (pintype "passive"))
      (node (ref "U$15") (pin "P$26") (pinfunction "C_P$26") (pintype "passive"))
      (node (ref "U$15") (pin "P$27") (pinfunction "C_P$27") (pintype "passive"))
      (node (ref "U$15") (pin "P$28") (pinfunction "C_P$28") (pintype "passive"))
      (node (ref "U$15") (pin "P$29") (pinfunction "C_P$29") (pintype "passive"))
      (node (ref "U$15") (pin "P$3") (pinfunction "C_P$3") (pintype "passive"))
      (node (ref "U$15") (pin "P$30") (pinfunction "C_P$30") (pintype "passive"))
      (node (ref "U$15") (pin "P$31") (pinfunction "C_P$31") (pintype "passive"))
      (node (ref "U$15") (pin "P$32") (pinfunction "C_P$32") (pintype "passive"))
      (node (ref "U$15") (pin "P$33") (pinfunction "C_P$33") (pintype "passive"))
      (node (ref "U$15") (pin "P$34") (pinfunction "C_P$34") (pintype "passive"))
      (node (ref "U$15") (pin "P$35") (pinfunction "C_P$35") (pintype "passive"))
      (node (ref "U$15") (pin "P$36") (pinfunction "C_P$36") (pintype "passive"))
      (node (ref "U$15") (pin "P$37") (pinfunction "C_P$37") (pintype "passive"))
      (node (ref "U$15") (pin "P$38") (pinfunction "C_P$38") (pintype "passive"))
      (node (ref "U$15") (pin "P$39") (pinfunction "C_P$39") (pintype "passive"))
      (node (ref "U$15") (pin "P$4") (pinfunction "C_P$4") (pintype "passive"))
      (node (ref "U$15") (pin "P$40") (pinfunction "C_P$40") (pintype "passive"))
      (node (ref "U$15") (pin "P$41") (pinfunction "C_P$41") (pintype "passive"))
      (node (ref "U$15") (pin "P$42") (pinfunction "C_P$42") (pintype "passive"))
      (node (ref "U$15") (pin "P$43") (pinfunction "C_P$43") (pintype "passive"))
      (node (ref "U$15") (pin "P$44") (pinfunction "C_P$44") (pintype "passive"))
      (node (ref "U$15") (pin "P$45") (pinfunction "C_P$45") (pintype "passive"))
      (node (ref "U$15") (pin "P$46") (pinfunction "C_P$46") (pintype "passive"))
      (node (ref "U$15") (pin "P$47") (pinfunction "C_P$47") (pintype "passive"))
      (node (ref "U$15") (pin "P$48") (pinfunction "C_P$48") (pintype "passive"))
      (node (ref "U$15") (pin "P$49") (pinfunction "C_P$49") (pintype "passive"))
      (node (ref "U$15") (pin "P$5") (pinfunction "C_P$5") (pintype "passive"))
      (node (ref "U$15") (pin "P$50") (pinfunction "C_P$50") (pintype "passive"))
      (node (ref "U$15") (pin "P$51") (pinfunction "C_P$51") (pintype "passive"))
      (node (ref "U$15") (pin "P$52") (pinfunction "C_P$52") (pintype "passive"))
      (node (ref "U$15") (pin "P$53") (pinfunction "C_P$53") (pintype "passive"))
      (node (ref "U$15") (pin "P$54") (pinfunction "C_P$54") (pintype "passive"))
      (node (ref "U$15") (pin "P$55") (pinfunction "C_P$55") (pintype "passive"))
      (node (ref "U$15") (pin "P$56") (pinfunction "C_P$56") (pintype "passive"))
      (node (ref "U$15") (pin "P$57") (pinfunction "C_P$57") (pintype "passive"))
      (node (ref "U$15") (pin "P$58") (pinfunction "C_P$58") (pintype "passive"))
      (node (ref "U$15") (pin "P$59") (pinfunction "C_P$59") (pintype "passive"))
      (node (ref "U$15") (pin "P$6") (pinfunction "C_P$6") (pintype "passive"))
      (node (ref "U$15") (pin "P$60") (pinfunction "C_P$60") (pintype "passive"))
      (node (ref "U$15") (pin "P$61") (pinfunction "C_P$61") (pintype "passive"))
      (node (ref "U$15") (pin "P$62") (pinfunction "C_P$62") (pintype "passive"))
      (node (ref "U$15") (pin "P$63") (pinfunction "C_P$63") (pintype "passive"))
      (node (ref "U$15") (pin "P$7") (pinfunction "C_P$7") (pintype "passive"))
      (node (ref "U$15") (pin "P$8") (pinfunction "C_P$8") (pintype "passive"))
      (node (ref "U$15") (pin "P$9") (pinfunction "C_P$9") (pintype "passive"))
    )
    (net (code "9") (name "AGND") (class "Default")
      (node (ref "B1") (pin "-") (pinfunction "-_-") (pintype "passive"))
      (node (ref "C1") (pin "-") (pinfunction "-_-") (pintype "passive"))
      (node (ref "C106") (pin "-") (pinfunction "-_-") (pintype "passive"))
      (node (ref "C13") (pin "2") (pinfunction "2_2") (pintype "passive"))
      (node (ref "C131") (pin "2") (pinfunction "2_2") (pintype "passive"))
      (node (ref "C132") (pin "1") (pinfunction "1_1") (pintype "passive"))
      (node (ref "C2") (pin "1") (pinfunction "1_1") (pintype "passive"))
      (node (ref "C9") (pin "2") (pinfunction "2_2") (pintype "passive"))
      (node (ref "D1") (pin "C") (pinfunction "C_C") (pintype "passive"))
      (node (ref "D28") (pin "C") (pinfunction "C_C") (pintype "passive"))
      (node (ref "IC11") (pin "4") (pinfunction "V-_4") (pintype "power_in"))
      (node (ref "Q5") (pin "C") (pinfunction "C_C") (pintype "passive"))
      (node (ref "R1") (pin "2") (pinfunction "2_2") (pintype "passive"))
      (node (ref "R43") (pin "1") (pinfunction "1_1") (pintype "passive"))
      (node (ref "U$2") (pin "4") (pinfunction "GND_4") (pintype "bidirectional"))
      (node (ref "U$4") (pin "P$2") (pinfunction "2_P$2") (pintype "passive"))
      (node (ref "X1") (pin "2") (pinfunction "S_2") (pintype "passive"))
      (node (ref "X3") (pin "2") (pinfunction "S_2") (pintype "passive"))
    )
    (net (code "10") (name "Net-(B1-AC1)") (class "Default")
      (node (ref "B1") (pin "AC2") (pinfunction "AC1_AC2") (pintype "passive"))
      (node (ref "X2") (pin "1") (pinfunction "S_1") (pintype "passive"))
    )
    (net (code "11") (name "Net-(B1-AC2)") (class "Default")
      (node (ref "B1") (pin "AC1") (pinfunction "AC2_AC1") (pintype "passive"))
      (node (ref "X2") (pin "2") (pinfunction "S_2") (pintype "passive"))
    )
    (net (code "12") (name "Net-(B3-AC1)") (class "Default")
      (node (ref "B3") (pin "AC2") (pinfunction "AC1_AC2") (pintype "passive"))
      (node (ref "X6") (pin "1") (pinfunction "S_1") (pintype "passive"))
    )
    (net (code "13") (name "Net-(B3-AC2)") (class "Default")
      (node (ref "B3") (pin "AC1") (pinfunction "AC2_AC1") (pintype "passive"))
      (node (ref "X6") (pin "2") (pinfunction "S_2") (pintype "passive"))
    )
    (net (code "14") (name "Net-(B5-AC1)") (class "Default")
      (node (ref "B5") (pin "AC2") (pinfunction "AC1_AC2") (pintype "passive"))
      (node (ref "X10") (pin "1") (pinfunction "S_1") (pintype "passive"))
    )
    (net (code "15") (name "Net-(B5-AC2)") (class "Default")
      (node (ref "B5") (pin "AC1") (pinfunction "AC2_AC1") (pintype "passive"))
      (node (ref "X10") (pin "2") (pinfunction "S_2") (pintype "passive"))
    )
    (net (code "16") (name "Net-(D1-PadA)") (class "Default")
      (node (ref "D1") (pin "A") (pinfunction "A_A") (pintype "passive"))
      (node (ref "Q1") (pin "B") (pinfunction "B_B") (pintype "passive"))
      (node (ref "R4") (pin "2") (pinfunction "2_2") (pintype "passive"))
    )
    (net (code "17") (name "Net-(D7-PadC)") (class "Default")
      (node (ref "D7") (pin "C") (pinfunction "C_C") (pintype "passive"))
      (node (ref "Q11") (pin "E") (pinfunction "E_E") (pintype "passive"))
    )
    (net (code "18") (name "Net-(D8-PadA)") (class "Default")
      (node (ref "D8") (pin "A") (pinfunction "A_A") (pintype "passive"))
      (node (ref "R16") (pin "1") (pinfunction "1_1") (pintype "passive"))
    )
    (net (code "19") (name "Net-(D9-PadA)") (class "Default")
      (node (ref "D9") (pin "A") (pinfunction "A_A") (pintype "passive"))
      (node (ref "Q10") (pin "B") (pinfunction "B_B") (pintype "passive"))
      (node (ref "R18") (pin "2") (pinfunction "2_2") (pintype "passive"))
    )
    (net (code "20") (name "Net-(D15-PadC)") (class "Default")
      (node (ref "D15") (pin "C") (pinfunction "C_C") (pintype "passive"))
      (node (ref "Q19") (pin "E") (pinfunction "E_E") (pintype "passive"))
    )
    (net (code "21") (name "Net-(D16-PadA)") (class "Default")
      (node (ref "D16") (pin "A") (pinfunction "A_A") (pintype "passive"))
      (node (ref "R32") (pin "1") (pinfunction "1_1") (pintype "passive"))
    )
    (net (code "22") (name "Net-(D17-PadA)") (class "Default")
      (node (ref "D17") (pin "A") (pinfunction "A_A") (pintype "passive"))
      (node (ref "Q18") (pin "B") (pinfunction "B_B") (pintype "passive"))
      (node (ref "R34") (pin "2") (pinfunction "2_2") (pintype "passive"))
    )
    (net (code "23") (name "Net-(D22-PadC)") (class "Default")
      (node (ref "D22") (pin "C") (pinfunction "C_C") (pintype "passive"))
      (node (ref "Q3") (pin "E") (pinfunction "E_E") (pintype "passive"))
    )
    (net (code "24") (name "Net-(D28-PadA)") (class "Default")
      (node (ref "D28") (pin "A") (pinfunction "A_A") (pintype "passive"))
      (node (ref "R47") (pin "1") (pinfunction "1_1") (pintype "passive"))
    )
    (net (code "25") (name "Net-(IC2-+IN)") (class "Default")
      (node (ref "C19") (pin "1") (pinfunction "1_1") (pintype "passive"))
      (node (ref "IC2") (pin "3") (pinfunction "+IN_3") (pintype "input"))
      (node (ref "U$8") (pin "6") (pinfunction "OUT_6") (pintype "bidirectional"))
    )
    (net (code "26") (name "Net-(IC2--IN)") (class "Default")
      (node (ref "C18") (pin "2") (pinfunction "2_2") (pintype "passive"))
      (node (ref "C22") (pin "2") (pinfunction "2_2") (pintype "passive"))
      (node (ref "IC2") (pin "2") (pinfunction "-IN_2") (pintype "input"))
      (node (ref "R14") (pin "2") (pinfunction "2_2") (pintype "passive"))
      (node (ref "R15") (pin "1") (pinfunction "1_1") (pintype "passive"))
    )
    (net (code "27") (name "Net-(IC2-OUT)") (class "Default")
      (node (ref "C22") (pin "1") (pinfunction "1_1") (pintype "passive"))
      (node (ref "IC2") (pin "6") (pinfunction "OUT_6") (pintype "output"))
      (node (ref "R13") (pin "1") (pinfunction "1_1") (pintype "passive"))
    )
    (net (code "28") (name "Net-(IC4-+IN)") (class "Default")
      (node (ref "C39") (pin "1") (pinfunction "1_1") (pintype "passive"))
      (node (ref "IC4") (pin "3") (pinfunction "+IN_3") (pintype "input"))
      (node (ref "U$14") (pin "6") (pinfunction "OUT_6") (pintype "bidirectional"))
    )
    (net (code "29") (name "Net-(IC4--IN)") (class "Default")
      (node (ref "C38") (pin "2") (pinfunction "2_2") (pintype "passive"))
      (node (ref "C42") (pin "2") (pinfunction "2_2") (pintype "passive"))
      (node (ref "IC4") (pin "2") (pinfunction "-IN_2") (pintype "input"))
      (node (ref "R30") (pin "2") (pinfunction "2_2") (pintype "passive"))
      (node (ref "R31") (pin "1") (pinfunction "1_1") (pintype "passive"))
    )
    (net (code "30") (name "Net-(IC4-OUT)") (class "Default")
      (node (ref "C42") (pin "1") (pinfunction "1_1") (pintype "passive"))
      (node (ref "IC4") (pin "6") (pinfunction "OUT_6") (pintype "output"))
      (node (ref "R29") (pin "1") (pinfunction "1_1") (pintype "passive"))
    )
    (net (code "31") (name "Net-(IC11-+IN)") (class "Default")
      (node (ref "C131") (pin "1") (pinfunction "1_1") (pintype "passive"))
      (node (ref "IC11") (pin "3") (pinfunction "+IN_3") (pintype "input"))
      (node (ref "U$2") (pin "6") (pinfunction "OUT_6") (pintype "bidirectional"))
    )
    (net (code "32") (name "Net-(IC11--IN)") (class "Default")
      (node (ref "C108") (pin "2") (pinfunction "2_2") (pintype "passive"))
      (node (ref "C3") (pin "2") (pinfunction "2_2") (pintype "passive"))
      (node (ref "IC11") (pin "2") (pinfunction "-IN_2") (pintype "input"))
      (node (ref "R43") (pin "2") (pinfunction "2_2") (pintype "passive"))
      (node (ref "R44") (pin "1") (pinfunction "1_1") (pintype "passive"))
    )
    (net (code "33") (name "Net-(IC11-OUT)") (class "Default")
      (node (ref "C3") (pin "1") (pinfunction "1_1") (pintype "passive"))
      (node (ref "IC11") (pin "6") (pinfunction "OUT_6") (pintype "output"))
      (node (ref "R42") (pin "1") (pinfunction "1_1") (pintype "passive"))
    )
    (net (code "34") (name "Net-(Q1-PadC)") (class "Default")
      (node (ref "Q1") (pin "C") (pinfunction "C_C") (pintype "passive"))
      (node (ref "Q3") (pin "B") (pinfunction "B_B") (pintype "passive"))
      (node (ref "Q3") (pin "C") (pinfunction "C_C") (pintype "passive"))
      (node (ref "Q4") (pin "B") (pinfunction "B_B") (pintype "passive"))
    )
    (net (code "35") (name "Net-(Q1-PadE)") (class "Default")
      (node (ref "Q1") (pin "E") (pinfunction "E_E") (pintype "passive"))
      (node (ref "R1") (pin "1") (pinfunction "1_1") (pintype "passive"))
    )
    (net (code "36") (name "Net-(Q4-PadE)") (class "Default")
      (node (ref "Q4") (pin "E") (pinfunction "E_E") (pintype "passive"))
      (node (ref "R37") (pin "2") (pinfunction "2_2") (pintype "passive"))
    )
    (net (code "37") (name "Net-(Q5-PadB)") (class "Default")
      (node (ref "Q5") (pin "B") (pinfunction "B_B") (pintype "passive"))
      (node (ref "R42") (pin "2") (pinfunction "2_2") (pintype "passive"))
    )
    (net (code "38") (name "Net-(Q5-PadE)") (class "Default")
      (node (ref "Q5") (pin "E") (pinfunction "E_E") (pintype "passive"))
      (node (ref "R38") (pin "2") (pinfunction "2_2") (pintype "passive"))
    )
    (net (code "39") (name "Net-(Q9-PadB)") (class "Default")
      (node (ref "Q9") (pin "B") (pinfunction "B_B") (pintype "passive"))
      (node (ref "R13") (pin "2") (pinfunction "2_2") (pintype "passive"))
    )
    (net (code "40") (name "Net-(Q9-PadE)") (class "Default")
      (node (ref "Q9") (pin "E") (pinfunction "E_E") (pintype "passive"))
      (node (ref "R12") (pin "2") (pinfunction "2_2") (pintype "passive"))
    )
    (net (code "41") (name "Net-(Q10-PadC)") (class "Default")
      (node (ref "Q10") (pin "C") (pinfunction "C_C") (pintype "passive"))
      (node (ref "Q11") (pin "B") (pinfunction "B_B") (pintype "passive"))
      (node (ref "Q11") (pin "C") (pinfunction "C_C") (pintype "passive"))
      (node (ref "Q12") (pin "B") (pinfunction "B_B") (pintype "passive"))
    )
    (net (code "42") (name "Net-(Q10-PadE)") (class "Default")
      (node (ref "Q10") (pin "E") (pinfunction "E_E") (pintype "passive"))
      (node (ref "R17") (pin "1") (pinfunction "1_1") (pintype "passive"))
    )
    (net (code "43") (name "Net-(Q12-PadE)") (class "Default")
      (node (ref "Q12") (pin "E") (pinfunction "E_E") (pintype "passive"))
      (node (ref "R11") (pin "2") (pinfunction "2_2") (pintype "passive"))
    )
    (net (code "44") (name "Net-(Q17-PadB)") (class "Default")
      (node (ref "Q17") (pin "B") (pinfunction "B_B") (pintype "passive"))
      (node (ref "R29") (pin "2") (pinfunction "2_2") (pintype "passive"))
    )
    (net (code "45") (name "Net-(Q17-PadE)") (class "Default")
      (node (ref "Q17") (pin "E") (pinfunction "E_E") (pintype "passive"))
      (node (ref "R28") (pin "2") (pinfunction "2_2") (pintype "passive"))
    )
    (net (code "46") (name "Net-(Q18-PadC)") (class "Default")
      (node (ref "Q18") (pin "C") (pinfunction "C_C") (pintype "passive"))
      (node (ref "Q19") (pin "B") (pinfunction "B_B") (pintype "passive"))
      (node (ref "Q19") (pin "C") (pinfunction "C_C") (pintype "passive"))
      (node (ref "Q20") (pin "B") (pinfunction "B_B") (pintype "passive"))
    )
    (net (code "47") (name "Net-(Q18-PadE)") (class "Default")
      (node (ref "Q18") (pin "E") (pinfunction "E_E") (pintype "passive"))
      (node (ref "R33") (pin "1") (pinfunction "1_1") (pintype "passive"))
    )
    (net (code "48") (name "Net-(Q20-PadE)") (class "Default")
      (node (ref "Q20") (pin "E") (pinfunction "E_E") (pintype "passive"))
      (node (ref "R27") (pin "2") (pinfunction "2_2") (pintype "passive"))
    )
    (net (code "49") (name "Net-(U$1-GND)") (class "Default")
      (node (ref "C102") (pin "2") (pinfunction "2_2") (pintype "passive"))
      (node (ref "R38") (pin "1") (pinfunction "1_1") (pintype "passive"))
      (node (ref "U$1") (pin "2") (pinfunction "GND_2") (pintype "passive"))
    )
    (net (code "50") (name "Net-(U$1-OUT)") (class "Default")
      (node (ref "C102") (pin "1") (pinfunction "1_1") (pintype "passive"))
      (node (ref "Q4") (pin "C") (pinfunction "C_C") (pintype "passive"))
      (node (ref "U$1") (pin "1") (pinfunction "OUT_1") (pintype "passive"))
      (node (ref "U$3") (pin "1") (pinfunction "B_1") (pintype "passive"))
    )
    (net (code "51") (name "Net-(U$7-GND)") (class "Default")
      (node (ref "C16") (pin "2") (pinfunction "2_2") (pintype "passive"))
      (node (ref "R12") (pin "1") (pinfunction "1_1") (pintype "passive"))
      (node (ref "U$7") (pin "2") (pinfunction "GND_2") (pintype "passive"))
    )
    (net (code "52") (name "Net-(U$7-OUT)") (class "Default")
      (node (ref "C16") (pin "1") (pinfunction "1_1") (pintype "passive"))
      (node (ref "Q12") (pin "C") (pinfunction "C_C") (pintype "passive"))
      (node (ref "U$7") (pin "1") (pinfunction "OUT_1") (pintype "passive"))
      (node (ref "U$9") (pin "1") (pinfunction "B_1") (pintype "passive"))
    )
    (net (code "53") (name "Net-(U$13-GND)") (class "Default")
      (node (ref "C36") (pin "2") (pinfunction "2_2") (pintype "passive"))
      (node (ref "R28") (pin "1") (pinfunction "1_1") (pintype "passive"))
      (node (ref "U$13") (pin "2") (pinfunction "GND_2") (pintype "passive"))
    )
    (net (code "54") (name "Net-(U$13-OUT)") (class "Default")
      (node (ref "C36") (pin "1") (pinfunction "1_1") (pintype "passive"))
      (node (ref "Q20") (pin "C") (pinfunction "C_C") (pintype "passive"))
      (node (ref "U$13") (pin "1") (pinfunction "OUT_1") (pintype "passive"))
      (node (ref "U$15") (pin "1") (pinfunction "B_1") (pintype "passive"))
    )
    (net (code "55") (name "unconnected-(IC2-CMP1-Pad1)") (class "Default")
      (node (ref "IC2") (pin "1") (pinfunction "CMP1_1") (pintype "passive"))
    )
    (net (code "56") (name "unconnected-(IC2-CMP2-Pad8)") (class "Default")
      (node (ref "IC2") (pin "8") (pinfunction "CMP2_8") (pintype "passive"))
    )
    (net (code "57") (name "unconnected-(IC4-CMP1-Pad1)") (class "Default")
      (node (ref "IC4") (pin "1") (pinfunction "CMP1_1") (pintype "passive"))
    )
    (net (code "58") (name "unconnected-(IC4-CMP2-Pad8)") (class "Default")
      (node (ref "IC4") (pin "8") (pinfunction "CMP2_8") (pintype "passive"))
    )
    (net (code "59") (name "unconnected-(IC11-CMP1-Pad1)") (class "Default")
      (node (ref "IC11") (pin "1") (pinfunction "CMP1_1") (pintype "passive"))
    )
    (net (code "60") (name "unconnected-(IC11-CMP2-Pad8)") (class "Default")
      (node (ref "IC11") (pin "8") (pinfunction "CMP2_8") (pintype "passive"))
    )
  )
)
